# BLOCK8.net
KiCad netlist of a schematic drawn in Altium Designer
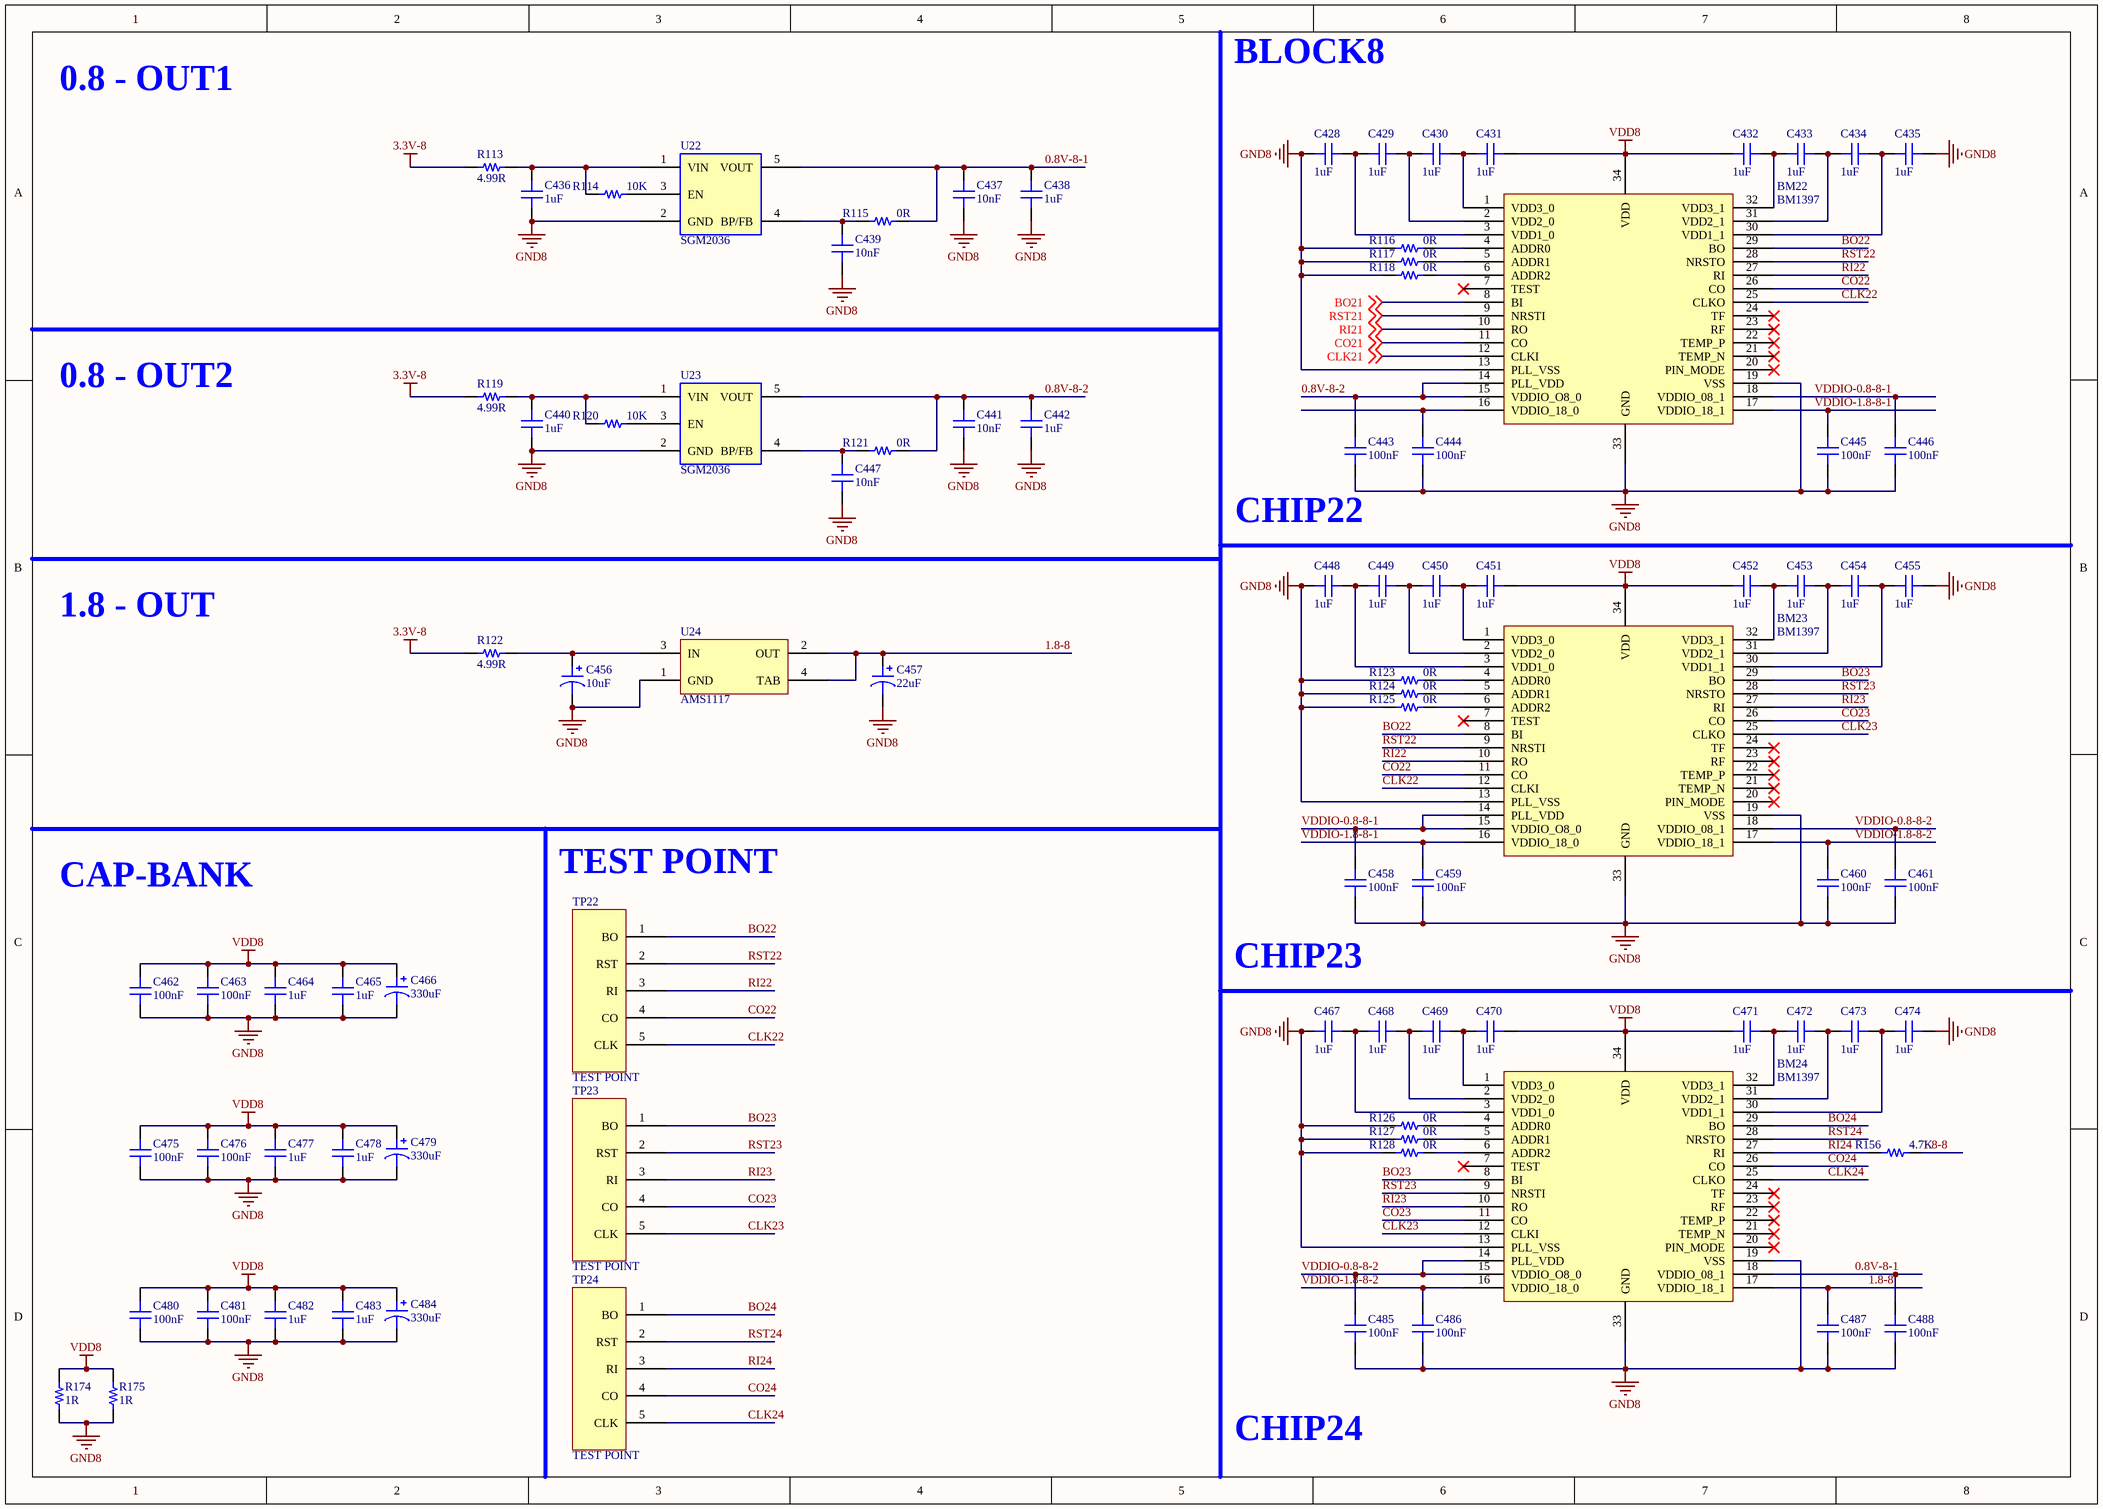
[diagram p0: BLOCK8.SchDoc]

(export (version "E")
  (design (tool "Eeschema 10.0.6"))
  (components
    (comp (ref "BM22") (value "BM1397") (footprint "BM1387") (libsource (lib "Miner_8TH") (part "BM1397_1")))
    (comp (ref "BM23") (value "BM1397") (footprint "BM1387") (libsource (lib "Miner_8TH") (part "BM1397_1")))
    (comp (ref "BM24") (value "BM1397") (footprint "BM1387") (libsource (lib "Miner_8TH") (part "BM1397_1")))
    (comp (ref "C428") (value "1uF") (footprint "CAP-SMD-0603") (libsource (lib "Miner_8TH") (part "CAP")))
    (comp (ref "C429") (value "1uF") (footprint "CAP-SMD-0603") (libsource (lib "Miner_8TH") (part "CAP")))
    (comp (ref "C430") (value "1uF") (footprint "CAP-SMD-0603") (libsource (lib "Miner_8TH") (part "CAP")))
    (comp (ref "C431") (value "1uF") (footprint "CAP-SMD-0603") (libsource (lib "Miner_8TH") (part "CAP")))
    (comp (ref "C432") (value "1uF") (footprint "CAP-SMD-0603") (libsource (lib "Miner_8TH") (part "CAP")))
    (comp (ref "C433") (value "1uF") (footprint "CAP-SMD-0603") (libsource (lib "Miner_8TH") (part "CAP")))
    (comp (ref "C434") (value "1uF") (footprint "CAP-SMD-0603") (libsource (lib "Miner_8TH") (part "CAP")))
    (comp (ref "C435") (value "1uF") (footprint "CAP-SMD-0603") (libsource (lib "Miner_8TH") (part "CAP")))
    (comp (ref "C436") (value "1uF") (footprint "CAP_SMD_0805") (libsource (lib "Miner_8TH") (part "CAP")))
    (comp (ref "C437") (value "10nF") (footprint "CAP_SMD_0805") (libsource (lib "Miner_8TH") (part "CAP")))
    (comp (ref "C438") (value "1uF") (footprint "CAP_SMD_0805") (libsource (lib "Miner_8TH") (part "CAP")))
    (comp (ref "C439") (value "10nF") (footprint "CAP_SMD_0805") (libsource (lib "Miner_8TH") (part "CAP")))
    (comp (ref "C440") (value "1uF") (footprint "CAP_SMD_0805") (libsource (lib "Miner_8TH") (part "CAP")))
    (comp (ref "C441") (value "10nF") (footprint "CAP_SMD_0805") (libsource (lib "Miner_8TH") (part "CAP")))
    (comp (ref "C442") (value "1uF") (footprint "CAP_SMD_0805") (libsource (lib "Miner_8TH") (part "CAP")))
    (comp (ref "C443") (value "100nF") (footprint "CAP_SMD_0805") (libsource (lib "Miner_8TH") (part "CAP")))
    (comp (ref "C444") (value "100nF") (footprint "CAP_SMD_0805") (libsource (lib "Miner_8TH") (part "CAP")))
    (comp (ref "C445") (value "100nF") (footprint "CAP_SMD_0805") (libsource (lib "Miner_8TH") (part "CAP")))
    (comp (ref "C446") (value "100nF") (footprint "CAP_SMD_0805") (libsource (lib "Miner_8TH") (part "CAP")))
    (comp (ref "C447") (value "10nF") (footprint "CAP_SMD_0805") (libsource (lib "Miner_8TH") (part "CAP")))
    (comp (ref "C448") (value "1uF") (footprint "CAP-SMD-0603") (libsource (lib "Miner_8TH") (part "CAP")))
    (comp (ref "C449") (value "1uF") (footprint "CAP-SMD-0603") (libsource (lib "Miner_8TH") (part "CAP")))
    (comp (ref "C450") (value "1uF") (footprint "CAP-SMD-0603") (libsource (lib "Miner_8TH") (part "CAP")))
    (comp (ref "C451") (value "1uF") (footprint "CAP-SMD-0603") (libsource (lib "Miner_8TH") (part "CAP")))
    (comp (ref "C452") (value "1uF") (footprint "CAP-SMD-0603") (libsource (lib "Miner_8TH") (part "CAP")))
    (comp (ref "C453") (value "1uF") (footprint "CAP-SMD-0603") (libsource (lib "Miner_8TH") (part "CAP")))
    (comp (ref "C454") (value "1uF") (footprint "CAP-SMD-0603") (libsource (lib "Miner_8TH") (part "CAP")))
    (comp (ref "C455") (value "1uF") (footprint "CAP-SMD-0603") (libsource (lib "Miner_8TH") (part "CAP")))
    (comp (ref "C456")
      (value "10uF")
      (footprint "CAP-TAN-CASE-A")
      (libsource (lib "Miner_8TH") (part "POLARIZED CAP"))
    )
    (comp (ref "C457")
      (value "22uF")
      (footprint "CAP-TAN-CASE-A")
      (libsource (lib "Miner_8TH") (part "POLARIZED CAP"))
    )
    (comp (ref "C458") (value "100nF") (footprint "CAP_SMD_0805") (libsource (lib "Miner_8TH") (part "CAP")))
    (comp (ref "C459") (value "100nF") (footprint "CAP_SMD_0805") (libsource (lib "Miner_8TH") (part "CAP")))
    (comp (ref "C460") (value "100nF") (footprint "CAP_SMD_0805") (libsource (lib "Miner_8TH") (part "CAP")))
    (comp (ref "C461") (value "100nF") (footprint "CAP_SMD_0805") (libsource (lib "Miner_8TH") (part "CAP")))
    (comp (ref "C462") (value "100nF") (footprint "CAP_SMD_0805") (libsource (lib "Miner_8TH") (part "CAP")))
    (comp (ref "C463") (value "100nF") (footprint "CAP_SMD_0805") (libsource (lib "Miner_8TH") (part "CAP")))
    (comp (ref "C464") (value "1uF") (footprint "CAP_SMD_0805") (libsource (lib "Miner_8TH") (part "CAP")))
    (comp (ref "C465") (value "1uF") (footprint "CAP_SMD_0805") (libsource (lib "Miner_8TH") (part "CAP")))
    (comp (ref "C466")
      (value "330uF")
      (footprint "CAP-TAN-CASE-E")
      (libsource (lib "Miner_8TH") (part "POLARIZED CAP"))
    )
    (comp (ref "C467") (value "1uF") (footprint "CAP-SMD-0603") (libsource (lib "Miner_8TH") (part "CAP")))
    (comp (ref "C468") (value "1uF") (footprint "CAP-SMD-0603") (libsource (lib "Miner_8TH") (part "CAP")))
    (comp (ref "C469") (value "1uF") (footprint "CAP-SMD-0603") (libsource (lib "Miner_8TH") (part "CAP")))
    (comp (ref "C470") (value "1uF") (footprint "CAP-SMD-0603") (libsource (lib "Miner_8TH") (part "CAP")))
    (comp (ref "C471") (value "1uF") (footprint "CAP-SMD-0603") (libsource (lib "Miner_8TH") (part "CAP")))
    (comp (ref "C472") (value "1uF") (footprint "CAP-SMD-0603") (libsource (lib "Miner_8TH") (part "CAP")))
    (comp (ref "C473") (value "1uF") (footprint "CAP-SMD-0603") (libsource (lib "Miner_8TH") (part "CAP")))
    (comp (ref "C474") (value "1uF") (footprint "CAP-SMD-0603") (libsource (lib "Miner_8TH") (part "CAP")))
    (comp (ref "C475") (value "100nF") (footprint "CAP_SMD_0805") (libsource (lib "Miner_8TH") (part "CAP")))
    (comp (ref "C476") (value "100nF") (footprint "CAP_SMD_0805") (libsource (lib "Miner_8TH") (part "CAP")))
    (comp (ref "C477") (value "1uF") (footprint "CAP_SMD_0805") (libsource (lib "Miner_8TH") (part "CAP")))
    (comp (ref "C478") (value "1uF") (footprint "CAP_SMD_0805") (libsource (lib "Miner_8TH") (part "CAP")))
    (comp (ref "C479")
      (value "330uF")
      (footprint "CAP-TAN-CASE-E")
      (libsource (lib "Miner_8TH") (part "POLARIZED CAP"))
    )
    (comp (ref "C480") (value "100nF") (footprint "CAP_SMD_0805") (libsource (lib "Miner_8TH") (part "CAP")))
    (comp (ref "C481") (value "100nF") (footprint "CAP_SMD_0805") (libsource (lib "Miner_8TH") (part "CAP")))
    (comp (ref "C482") (value "1uF") (footprint "CAP_SMD_0805") (libsource (lib "Miner_8TH") (part "CAP")))
    (comp (ref "C483") (value "1uF") (footprint "CAP_SMD_0805") (libsource (lib "Miner_8TH") (part "CAP")))
    (comp (ref "C484")
      (value "330uF")
      (footprint "CAP-TAN-CASE-E")
      (libsource (lib "Miner_8TH") (part "POLARIZED CAP"))
    )
    (comp (ref "C485") (value "100nF") (footprint "CAP_SMD_0805") (libsource (lib "Miner_8TH") (part "CAP")))
    (comp (ref "C486") (value "100nF") (footprint "CAP_SMD_0805") (libsource (lib "Miner_8TH") (part "CAP")))
    (comp (ref "C487") (value "100nF") (footprint "CAP_SMD_0805") (libsource (lib "Miner_8TH") (part "CAP")))
    (comp (ref "C488") (value "100nF") (footprint "CAP_SMD_0805") (libsource (lib "Miner_8TH") (part "CAP")))
    (comp (ref "R113") (value "4.99R") (footprint "RES-SMD-1206") (libsource (lib "Miner_8TH") (part "RES")))
    (comp (ref "R114") (value "10K") (footprint "RES-SMD-0402") (libsource (lib "Miner_8TH") (part "RES")))
    (comp (ref "R115") (value "0R") (footprint "RES-SMD-0402") (libsource (lib "Miner_8TH") (part "RES")))
    (comp (ref "R116") (value "0R") (footprint "RES-SMD-0402") (libsource (lib "Miner_8TH") (part "RES")))
    (comp (ref "R117") (value "0R") (footprint "RES-SMD-0402") (libsource (lib "Miner_8TH") (part "RES")))
    (comp (ref "R118") (value "0R") (footprint "RES-SMD-0402") (libsource (lib "Miner_8TH") (part "RES")))
    (comp (ref "R119") (value "4.99R") (footprint "RES-SMD-1206") (libsource (lib "Miner_8TH") (part "RES")))
    (comp (ref "R120") (value "10K") (footprint "RES-SMD-0402") (libsource (lib "Miner_8TH") (part "RES")))
    (comp (ref "R121") (value "0R") (footprint "RES-SMD-0402") (libsource (lib "Miner_8TH") (part "RES")))
    (comp (ref "R122") (value "4.99R") (footprint "RES-SMD-1206") (libsource (lib "Miner_8TH") (part "RES")))
    (comp (ref "R123") (value "0R") (footprint "RES-SMD-0402") (libsource (lib "Miner_8TH") (part "RES")))
    (comp (ref "R124") (value "0R") (footprint "RES-SMD-0402") (libsource (lib "Miner_8TH") (part "RES")))
    (comp (ref "R125") (value "0R") (footprint "RES-SMD-0402") (libsource (lib "Miner_8TH") (part "RES")))
    (comp (ref "R126") (value "0R") (footprint "RES-SMD-0402") (libsource (lib "Miner_8TH") (part "RES")))
    (comp (ref "R127") (value "0R") (footprint "RES-SMD-0402") (libsource (lib "Miner_8TH") (part "RES")))
    (comp (ref "R128") (value "0R") (footprint "RES-SMD-0402") (libsource (lib "Miner_8TH") (part "RES")))
    (comp (ref "R156") (value "4.7K") (footprint "RES-SMD-0402") (libsource (lib "Miner_8TH") (part "RES")))
    (comp (ref "R174") (value "1R") (footprint "RES-SMD-1210") (libsource (lib "Miner_8TH") (part "RES")))
    (comp (ref "R175") (value "1R") (footprint "RES-SMD-1210") (libsource (lib "Miner_8TH") (part "RES")))
    (comp (ref "TP22")
      (value "TEST POINT")
      (footprint "TEST_POINT")
      (libsource (lib "Miner_8TH") (part "TEST POINT"))
    )
    (comp (ref "TP23")
      (value "TEST POINT")
      (footprint "TEST_POINT")
      (libsource (lib "Miner_8TH") (part "TEST POINT"))
    )
    (comp (ref "TP24")
      (value "TEST POINT")
      (footprint "TEST_POINT")
      (libsource (lib "Miner_8TH") (part "TEST POINT"))
    )
    (comp (ref "U22")
      (value "SGM2036")
      (footprint "SOT23-5PIN")
      (libsource (lib "Miner_8TH") (part "SGM2036"))
    )
    (comp (ref "U23")
      (value "SGM2036")
      (footprint "SOT23-5PIN")
      (libsource (lib "Miner_8TH") (part "SGM2036"))
    )
    (comp (ref "U24") (value "AMS1117") (footprint "AMS1117") (libsource (lib "Miner_8TH") (part "AMS1117")))
  )
  (nets
    (net (code "1") (name "/0.8V-8-1") (class "Default")
      (node (ref "BM24") (pin "18") (pinfunction "VDDIO_08_1_18") (pintype "passive"))
      (node (ref "C437") (pin "2") (pinfunction "2_2") (pintype "passive"))
      (node (ref "C438") (pin "2") (pinfunction "2_2") (pintype "passive"))
      (node (ref "C488") (pin "2") (pinfunction "2_2") (pintype "passive"))
      (node (ref "R115") (pin "2") (pinfunction "2_2") (pintype "passive"))
      (node (ref "U22") (pin "5") (pinfunction "VOUT_5") (pintype "passive"))
    )
    (net (code "2") (name "/0.8V-8-2") (class "Default")
      (node (ref "BM22") (pin "14") (pinfunction "PLL_VDD_14") (pintype "passive"))
      (node (ref "BM22") (pin "15") (pinfunction "VDDIO_O8_0_15") (pintype "passive"))
      (node (ref "C441") (pin "2") (pinfunction "2_2") (pintype "passive"))
      (node (ref "C442") (pin "2") (pinfunction "2_2") (pintype "passive"))
      (node (ref "C443") (pin "2") (pinfunction "2_2") (pintype "passive"))
      (node (ref "R121") (pin "2") (pinfunction "2_2") (pintype "passive"))
      (node (ref "U23") (pin "5") (pinfunction "VOUT_5") (pintype "passive"))
    )
    (net (code "3") (name "/1.8-8") (class "Default")
      (node (ref "BM24") (pin "17") (pinfunction "VDDIO_18_1_17") (pintype "passive"))
      (node (ref "C457") (pin "1") (pinfunction "1_1") (pintype "passive"))
      (node (ref "C487") (pin "2") (pinfunction "2_2") (pintype "passive"))
      (node (ref "R156") (pin "2") (pinfunction "2_2") (pintype "passive"))
      (node (ref "U24") (pin "2") (pinfunction "OUT_2") (pintype "passive"))
      (node (ref "U24") (pin "4") (pinfunction "TAB_4") (pintype "passive"))
    )
    (net (code "4") (name "/BO22") (class "Default")
      (node (ref "BM22") (pin "29") (pinfunction "BO_29") (pintype "passive"))
      (node (ref "BM23") (pin "8") (pinfunction "BI_8") (pintype "passive"))
      (node (ref "TP22") (pin "1") (pinfunction "BO_1") (pintype "passive"))
    )
    (net (code "5") (name "/BO23") (class "Default")
      (node (ref "BM23") (pin "29") (pinfunction "BO_29") (pintype "passive"))
      (node (ref "BM24") (pin "8") (pinfunction "BI_8") (pintype "passive"))
      (node (ref "TP23") (pin "1") (pinfunction "BO_1") (pintype "passive"))
    )
    (net (code "6") (name "/BO24") (class "Default")
      (node (ref "BM24") (pin "29") (pinfunction "BO_29") (pintype "passive"))
      (node (ref "TP24") (pin "1") (pinfunction "BO_1") (pintype "passive"))
    )
    (net (code "7") (name "/CLK22") (class "Default")
      (node (ref "BM22") (pin "25") (pinfunction "CLKO_25") (pintype "passive"))
      (node (ref "BM23") (pin "12") (pinfunction "CLKI_12") (pintype "passive"))
      (node (ref "TP22") (pin "5") (pinfunction "CLK_5") (pintype "passive"))
    )
    (net (code "8") (name "/CLK23") (class "Default")
      (node (ref "BM23") (pin "25") (pinfunction "CLKO_25") (pintype "passive"))
      (node (ref "BM24") (pin "12") (pinfunction "CLKI_12") (pintype "passive"))
      (node (ref "TP23") (pin "5") (pinfunction "CLK_5") (pintype "passive"))
    )
    (net (code "9") (name "/CLK24") (class "Default")
      (node (ref "BM24") (pin "25") (pinfunction "CLKO_25") (pintype "passive"))
      (node (ref "TP24") (pin "5") (pinfunction "CLK_5") (pintype "passive"))
    )
    (net (code "10") (name "/CO22") (class "Default")
      (node (ref "BM22") (pin "26") (pinfunction "CO_26") (pintype "passive"))
      (node (ref "BM23") (pin "11") (pinfunction "CO_11") (pintype "passive"))
      (node (ref "TP22") (pin "4") (pinfunction "CO_4") (pintype "passive"))
    )
    (net (code "11") (name "/CO23") (class "Default")
      (node (ref "BM23") (pin "26") (pinfunction "CO_26") (pintype "passive"))
      (node (ref "BM24") (pin "11") (pinfunction "CO_11") (pintype "passive"))
      (node (ref "TP23") (pin "4") (pinfunction "CO_4") (pintype "passive"))
    )
    (net (code "12") (name "/CO24") (class "Default")
      (node (ref "BM24") (pin "26") (pinfunction "CO_26") (pintype "passive"))
      (node (ref "TP24") (pin "4") (pinfunction "CO_4") (pintype "passive"))
    )
    (net (code "13") (name "/RI22") (class "Default")
      (node (ref "BM22") (pin "27") (pinfunction "RI_27") (pintype "passive"))
      (node (ref "BM23") (pin "10") (pinfunction "RO_10") (pintype "passive"))
      (node (ref "TP22") (pin "3") (pinfunction "RI_3") (pintype "passive"))
    )
    (net (code "14") (name "/RI23") (class "Default")
      (node (ref "BM23") (pin "27") (pinfunction "RI_27") (pintype "passive"))
      (node (ref "BM24") (pin "10") (pinfunction "RO_10") (pintype "passive"))
      (node (ref "TP23") (pin "3") (pinfunction "RI_3") (pintype "passive"))
    )
    (net (code "15") (name "/RI24") (class "Default")
      (node (ref "BM24") (pin "27") (pinfunction "RI_27") (pintype "passive"))
      (node (ref "R156") (pin "1") (pinfunction "1_1") (pintype "passive"))
      (node (ref "TP24") (pin "3") (pinfunction "RI_3") (pintype "passive"))
    )
    (net (code "16") (name "/RST22") (class "Default")
      (node (ref "BM22") (pin "28") (pinfunction "NRSTO_28") (pintype "passive"))
      (node (ref "BM23") (pin "9") (pinfunction "NRSTI_9") (pintype "passive"))
      (node (ref "TP22") (pin "2") (pinfunction "RST_2") (pintype "passive"))
    )
    (net (code "17") (name "/RST23") (class "Default")
      (node (ref "BM23") (pin "28") (pinfunction "NRSTO_28") (pintype "passive"))
      (node (ref "BM24") (pin "9") (pinfunction "NRSTI_9") (pintype "passive"))
      (node (ref "TP23") (pin "2") (pinfunction "RST_2") (pintype "passive"))
    )
    (net (code "18") (name "/RST24") (class "Default")
      (node (ref "BM24") (pin "28") (pinfunction "NRSTO_28") (pintype "passive"))
      (node (ref "TP24") (pin "2") (pinfunction "RST_2") (pintype "passive"))
    )
    (net (code "19") (name "/VDDIO-0.8-8-1") (class "Default")
      (node (ref "BM22") (pin "18") (pinfunction "VDDIO_08_1_18") (pintype "passive"))
      (node (ref "BM23") (pin "14") (pinfunction "PLL_VDD_14") (pintype "passive"))
      (node (ref "BM23") (pin "15") (pinfunction "VDDIO_O8_0_15") (pintype "passive"))
      (node (ref "C446") (pin "2") (pinfunction "2_2") (pintype "passive"))
      (node (ref "C458") (pin "2") (pinfunction "2_2") (pintype "passive"))
    )
    (net (code "20") (name "/VDDIO-0.8-8-2") (class "Default")
      (node (ref "BM23") (pin "18") (pinfunction "VDDIO_08_1_18") (pintype "passive"))
      (node (ref "BM24") (pin "14") (pinfunction "PLL_VDD_14") (pintype "passive"))
      (node (ref "BM24") (pin "15") (pinfunction "VDDIO_O8_0_15") (pintype "passive"))
      (node (ref "C461") (pin "2") (pinfunction "2_2") (pintype "passive"))
      (node (ref "C485") (pin "2") (pinfunction "2_2") (pintype "passive"))
    )
    (net (code "21") (name "/VDDIO-1.8-8-1") (class "Default")
      (node (ref "BM22") (pin "17") (pinfunction "VDDIO_18_1_17") (pintype "passive"))
      (node (ref "BM23") (pin "16") (pinfunction "VDDIO_18_0_16") (pintype "passive"))
      (node (ref "C445") (pin "2") (pinfunction "2_2") (pintype "passive"))
      (node (ref "C459") (pin "2") (pinfunction "2_2") (pintype "passive"))
    )
    (net (code "22") (name "/VDDIO-1.8-8-2") (class "Default")
      (node (ref "BM23") (pin "17") (pinfunction "VDDIO_18_1_17") (pintype "passive"))
      (node (ref "BM24") (pin "16") (pinfunction "VDDIO_18_0_16") (pintype "passive"))
      (node (ref "C460") (pin "2") (pinfunction "2_2") (pintype "passive"))
      (node (ref "C486") (pin "2") (pinfunction "2_2") (pintype "passive"))
    )
    (net (code "23") (name "3.3V-8") (class "Default")
      (node (ref "R113") (pin "1") (pinfunction "1_1") (pintype "passive"))
      (node (ref "R119") (pin "1") (pinfunction "1_1") (pintype "passive"))
      (node (ref "R122") (pin "1") (pinfunction "1_1") (pintype "passive"))
    )
    (net (code "24") (name "BO21") (class "Default")
      (node (ref "BM22") (pin "8") (pinfunction "BI_8") (pintype "passive"))
    )
    (net (code "25") (name "CLK21") (class "Default")
      (node (ref "BM22") (pin "12") (pinfunction "CLKI_12") (pintype "passive"))
    )
    (net (code "26") (name "CO21") (class "Default")
      (node (ref "BM22") (pin "11") (pinfunction "CO_11") (pintype "passive"))
    )
    (net (code "27") (name "GND8") (class "Default")
      (node (ref "BM22") (pin "13") (pinfunction "PLL_VSS_13") (pintype "passive"))
      (node (ref "BM22") (pin "19") (pinfunction "VSS_19") (pintype "passive"))
      (node (ref "BM22") (pin "33") (pinfunction "GND_33") (pintype "passive"))
      (node (ref "BM23") (pin "13") (pinfunction "PLL_VSS_13") (pintype "passive"))
      (node (ref "BM23") (pin "19") (pinfunction "VSS_19") (pintype "passive"))
      (node (ref "BM23") (pin "33") (pinfunction "GND_33") (pintype "passive"))
      (node (ref "BM24") (pin "13") (pinfunction "PLL_VSS_13") (pintype "passive"))
      (node (ref "BM24") (pin "19") (pinfunction "VSS_19") (pintype "passive"))
      (node (ref "BM24") (pin "33") (pinfunction "GND_33") (pintype "passive"))
      (node (ref "C428") (pin "1") (pinfunction "1_1") (pintype "passive"))
      (node (ref "C435") (pin "2") (pinfunction "2_2") (pintype "passive"))
      (node (ref "C436") (pin "1") (pinfunction "1_1") (pintype "passive"))
      (node (ref "C437") (pin "1") (pinfunction "1_1") (pintype "passive"))
      (node (ref "C438") (pin "1") (pinfunction "1_1") (pintype "passive"))
      (node (ref "C439") (pin "1") (pinfunction "1_1") (pintype "passive"))
      (node (ref "C440") (pin "1") (pinfunction "1_1") (pintype "passive"))
      (node (ref "C441") (pin "1") (pinfunction "1_1") (pintype "passive"))
      (node (ref "C442") (pin "1") (pinfunction "1_1") (pintype "passive"))
      (node (ref "C443") (pin "1") (pinfunction "1_1") (pintype "passive"))
      (node (ref "C444") (pin "1") (pinfunction "1_1") (pintype "passive"))
      (node (ref "C445") (pin "1") (pinfunction "1_1") (pintype "passive"))
      (node (ref "C446") (pin "1") (pinfunction "1_1") (pintype "passive"))
      (node (ref "C447") (pin "1") (pinfunction "1_1") (pintype "passive"))
      (node (ref "C448") (pin "1") (pinfunction "1_1") (pintype "passive"))
      (node (ref "C455") (pin "2") (pinfunction "2_2") (pintype "passive"))
      (node (ref "C456") (pin "2") (pinfunction "2_2") (pintype "passive"))
      (node (ref "C457") (pin "2") (pinfunction "2_2") (pintype "passive"))
      (node (ref "C458") (pin "1") (pinfunction "1_1") (pintype "passive"))
      (node (ref "C459") (pin "1") (pinfunction "1_1") (pintype "passive"))
      (node (ref "C460") (pin "1") (pinfunction "1_1") (pintype "passive"))
      (node (ref "C461") (pin "1") (pinfunction "1_1") (pintype "passive"))
      (node (ref "C462") (pin "1") (pinfunction "1_1") (pintype "passive"))
      (node (ref "C463") (pin "1") (pinfunction "1_1") (pintype "passive"))
      (node (ref "C464") (pin "1") (pinfunction "1_1") (pintype "passive"))
      (node (ref "C465") (pin "1") (pinfunction "1_1") (pintype "passive"))
      (node (ref "C466") (pin "2") (pinfunction "2_2") (pintype "passive"))
      (node (ref "C467") (pin "1") (pinfunction "1_1") (pintype "passive"))
      (node (ref "C474") (pin "2") (pinfunction "2_2") (pintype "passive"))
      (node (ref "C475") (pin "1") (pinfunction "1_1") (pintype "passive"))
      (node (ref "C476") (pin "1") (pinfunction "1_1") (pintype "passive"))
      (node (ref "C477") (pin "1") (pinfunction "1_1") (pintype "passive"))
      (node (ref "C478") (pin "1") (pinfunction "1_1") (pintype "passive"))
      (node (ref "C479") (pin "2") (pinfunction "2_2") (pintype "passive"))
      (node (ref "C480") (pin "1") (pinfunction "1_1") (pintype "passive"))
      (node (ref "C481") (pin "1") (pinfunction "1_1") (pintype "passive"))
      (node (ref "C482") (pin "1") (pinfunction "1_1") (pintype "passive"))
      (node (ref "C483") (pin "1") (pinfunction "1_1") (pintype "passive"))
      (node (ref "C484") (pin "2") (pinfunction "2_2") (pintype "passive"))
      (node (ref "C485") (pin "1") (pinfunction "1_1") (pintype "passive"))
      (node (ref "C486") (pin "1") (pinfunction "1_1") (pintype "passive"))
      (node (ref "C487") (pin "1") (pinfunction "1_1") (pintype "passive"))
      (node (ref "C488") (pin "1") (pinfunction "1_1") (pintype "passive"))
      (node (ref "R116") (pin "1") (pinfunction "1_1") (pintype "passive"))
      (node (ref "R117") (pin "1") (pinfunction "1_1") (pintype "passive"))
      (node (ref "R118") (pin "1") (pinfunction "1_1") (pintype "passive"))
      (node (ref "R123") (pin "1") (pinfunction "1_1") (pintype "passive"))
      (node (ref "R124") (pin "1") (pinfunction "1_1") (pintype "passive"))
      (node (ref "R125") (pin "1") (pinfunction "1_1") (pintype "passive"))
      (node (ref "R126") (pin "1") (pinfunction "1_1") (pintype "passive"))
      (node (ref "R127") (pin "1") (pinfunction "1_1") (pintype "passive"))
      (node (ref "R128") (pin "1") (pinfunction "1_1") (pintype "passive"))
      (node (ref "R174") (pin "1") (pinfunction "1_1") (pintype "passive"))
      (node (ref "R175") (pin "1") (pinfunction "1_1") (pintype "passive"))
      (node (ref "U22") (pin "2") (pinfunction "GND_2") (pintype "passive"))
      (node (ref "U23") (pin "2") (pinfunction "GND_2") (pintype "passive"))
      (node (ref "U24") (pin "1") (pinfunction "GND_1") (pintype "passive"))
    )
    (net (code "28") (name "Net-(BM22-ADDR0)") (class "Default")
      (node (ref "BM22") (pin "4") (pinfunction "ADDR0_4") (pintype "passive"))
      (node (ref "R116") (pin "2") (pinfunction "2_2") (pintype "passive"))
    )
    (net (code "29") (name "Net-(BM22-ADDR1)") (class "Default")
      (node (ref "BM22") (pin "5") (pinfunction "ADDR1_5") (pintype "passive"))
      (node (ref "R117") (pin "2") (pinfunction "2_2") (pintype "passive"))
    )
    (net (code "30") (name "Net-(BM22-ADDR2)") (class "Default")
      (node (ref "BM22") (pin "6") (pinfunction "ADDR2_6") (pintype "passive"))
      (node (ref "R118") (pin "2") (pinfunction "2_2") (pintype "passive"))
    )
    (net (code "31") (name "Net-(BM22-VDD1_0)") (class "Default")
      (node (ref "BM22") (pin "3") (pinfunction "VDD1_0_3") (pintype "passive"))
      (node (ref "C428") (pin "2") (pinfunction "2_2") (pintype "passive"))
      (node (ref "C429") (pin "1") (pinfunction "1_1") (pintype "passive"))
    )
    (net (code "32") (name "Net-(BM22-VDD1_1)") (class "Default")
      (node (ref "BM22") (pin "30") (pinfunction "VDD1_1_30") (pintype "passive"))
      (node (ref "C434") (pin "2") (pinfunction "2_2") (pintype "passive"))
      (node (ref "C435") (pin "1") (pinfunction "1_1") (pintype "passive"))
    )
    (net (code "33") (name "Net-(BM22-VDD2_0)") (class "Default")
      (node (ref "BM22") (pin "2") (pinfunction "VDD2_0_2") (pintype "passive"))
      (node (ref "C429") (pin "2") (pinfunction "2_2") (pintype "passive"))
      (node (ref "C430") (pin "1") (pinfunction "1_1") (pintype "passive"))
    )
    (net (code "34") (name "Net-(BM22-VDD2_1)") (class "Default")
      (node (ref "BM22") (pin "31") (pinfunction "VDD2_1_31") (pintype "passive"))
      (node (ref "C433") (pin "2") (pinfunction "2_2") (pintype "passive"))
      (node (ref "C434") (pin "1") (pinfunction "1_1") (pintype "passive"))
    )
    (net (code "35") (name "Net-(BM22-VDD3_0)") (class "Default")
      (node (ref "BM22") (pin "1") (pinfunction "VDD3_0_1") (pintype "passive"))
      (node (ref "C430") (pin "2") (pinfunction "2_2") (pintype "passive"))
      (node (ref "C431") (pin "1") (pinfunction "1_1") (pintype "passive"))
    )
    (net (code "36") (name "Net-(BM22-VDD3_1)") (class "Default")
      (node (ref "BM22") (pin "32") (pinfunction "VDD3_1_32") (pintype "passive"))
      (node (ref "C432") (pin "2") (pinfunction "2_2") (pintype "passive"))
      (node (ref "C433") (pin "1") (pinfunction "1_1") (pintype "passive"))
    )
    (net (code "37") (name "Net-(BM22-VDDIO_18_0)") (class "Default")
      (node (ref "BM22") (pin "16") (pinfunction "VDDIO_18_0_16") (pintype "passive"))
      (node (ref "C444") (pin "2") (pinfunction "2_2") (pintype "passive"))
    )
    (net (code "38") (name "Net-(BM23-ADDR0)") (class "Default")
      (node (ref "BM23") (pin "4") (pinfunction "ADDR0_4") (pintype "passive"))
      (node (ref "R123") (pin "2") (pinfunction "2_2") (pintype "passive"))
    )
    (net (code "39") (name "Net-(BM23-ADDR1)") (class "Default")
      (node (ref "BM23") (pin "5") (pinfunction "ADDR1_5") (pintype "passive"))
      (node (ref "R124") (pin "2") (pinfunction "2_2") (pintype "passive"))
    )
    (net (code "40") (name "Net-(BM23-ADDR2)") (class "Default")
      (node (ref "BM23") (pin "6") (pinfunction "ADDR2_6") (pintype "passive"))
      (node (ref "R125") (pin "2") (pinfunction "2_2") (pintype "passive"))
    )
    (net (code "41") (name "Net-(BM23-VDD1_0)") (class "Default")
      (node (ref "BM23") (pin "3") (pinfunction "VDD1_0_3") (pintype "passive"))
      (node (ref "C448") (pin "2") (pinfunction "2_2") (pintype "passive"))
      (node (ref "C449") (pin "1") (pinfunction "1_1") (pintype "passive"))
    )
    (net (code "42") (name "Net-(BM23-VDD1_1)") (class "Default")
      (node (ref "BM23") (pin "30") (pinfunction "VDD1_1_30") (pintype "passive"))
      (node (ref "C454") (pin "2") (pinfunction "2_2") (pintype "passive"))
      (node (ref "C455") (pin "1") (pinfunction "1_1") (pintype "passive"))
    )
    (net (code "43") (name "Net-(BM23-VDD2_0)") (class "Default")
      (node (ref "BM23") (pin "2") (pinfunction "VDD2_0_2") (pintype "passive"))
      (node (ref "C449") (pin "2") (pinfunction "2_2") (pintype "passive"))
      (node (ref "C450") (pin "1") (pinfunction "1_1") (pintype "passive"))
    )
    (net (code "44") (name "Net-(BM23-VDD2_1)") (class "Default")
      (node (ref "BM23") (pin "31") (pinfunction "VDD2_1_31") (pintype "passive"))
      (node (ref "C453") (pin "2") (pinfunction "2_2") (pintype "passive"))
      (node (ref "C454") (pin "1") (pinfunction "1_1") (pintype "passive"))
    )
    (net (code "45") (name "Net-(BM23-VDD3_0)") (class "Default")
      (node (ref "BM23") (pin "1") (pinfunction "VDD3_0_1") (pintype "passive"))
      (node (ref "C450") (pin "2") (pinfunction "2_2") (pintype "passive"))
      (node (ref "C451") (pin "1") (pinfunction "1_1") (pintype "passive"))
    )
    (net (code "46") (name "Net-(BM23-VDD3_1)") (class "Default")
      (node (ref "BM23") (pin "32") (pinfunction "VDD3_1_32") (pintype "passive"))
      (node (ref "C452") (pin "2") (pinfunction "2_2") (pintype "passive"))
      (node (ref "C453") (pin "1") (pinfunction "1_1") (pintype "passive"))
    )
    (net (code "47") (name "Net-(BM24-ADDR0)") (class "Default")
      (node (ref "BM24") (pin "4") (pinfunction "ADDR0_4") (pintype "passive"))
      (node (ref "R126") (pin "2") (pinfunction "2_2") (pintype "passive"))
    )
    (net (code "48") (name "Net-(BM24-ADDR1)") (class "Default")
      (node (ref "BM24") (pin "5") (pinfunction "ADDR1_5") (pintype "passive"))
      (node (ref "R127") (pin "2") (pinfunction "2_2") (pintype "passive"))
    )
    (net (code "49") (name "Net-(BM24-ADDR2)") (class "Default")
      (node (ref "BM24") (pin "6") (pinfunction "ADDR2_6") (pintype "passive"))
      (node (ref "R128") (pin "2") (pinfunction "2_2") (pintype "passive"))
    )
    (net (code "50") (name "Net-(BM24-VDD1_0)") (class "Default")
      (node (ref "BM24") (pin "3") (pinfunction "VDD1_0_3") (pintype "passive"))
      (node (ref "C467") (pin "2") (pinfunction "2_2") (pintype "passive"))
      (node (ref "C468") (pin "1") (pinfunction "1_1") (pintype "passive"))
    )
    (net (code "51") (name "Net-(BM24-VDD1_1)") (class "Default")
      (node (ref "BM24") (pin "30") (pinfunction "VDD1_1_30") (pintype "passive"))
      (node (ref "C473") (pin "2") (pinfunction "2_2") (pintype "passive"))
      (node (ref "C474") (pin "1") (pinfunction "1_1") (pintype "passive"))
    )
    (net (code "52") (name "Net-(BM24-VDD2_0)") (class "Default")
      (node (ref "BM24") (pin "2") (pinfunction "VDD2_0_2") (pintype "passive"))
      (node (ref "C468") (pin "2") (pinfunction "2_2") (pintype "passive"))
      (node (ref "C469") (pin "1") (pinfunction "1_1") (pintype "passive"))
    )
    (net (code "53") (name "Net-(BM24-VDD2_1)") (class "Default")
      (node (ref "BM24") (pin "31") (pinfunction "VDD2_1_31") (pintype "passive"))
      (node (ref "C472") (pin "2") (pinfunction "2_2") (pintype "passive"))
      (node (ref "C473") (pin "1") (pinfunction "1_1") (pintype "passive"))
    )
    (net (code "54") (name "Net-(BM24-VDD3_0)") (class "Default")
      (node (ref "BM24") (pin "1") (pinfunction "VDD3_0_1") (pintype "passive"))
      (node (ref "C469") (pin "2") (pinfunction "2_2") (pintype "passive"))
      (node (ref "C470") (pin "1") (pinfunction "1_1") (pintype "passive"))
    )
    (net (code "55") (name "Net-(BM24-VDD3_1)") (class "Default")
      (node (ref "BM24") (pin "32") (pinfunction "VDD3_1_32") (pintype "passive"))
      (node (ref "C471") (pin "2") (pinfunction "2_2") (pintype "passive"))
      (node (ref "C472") (pin "1") (pinfunction "1_1") (pintype "passive"))
    )
    (net (code "56") (name "Net-(U22-BP{slash}FB)") (class "Default")
      (node (ref "C439") (pin "2") (pinfunction "2_2") (pintype "passive"))
      (node (ref "R115") (pin "1") (pinfunction "1_1") (pintype "passive"))
      (node (ref "U22") (pin "4") (pinfunction "BP/FB_4") (pintype "passive"))
    )
    (net (code "57") (name "Net-(U22-EN)") (class "Default")
      (node (ref "R114") (pin "2") (pinfunction "2_2") (pintype "passive"))
      (node (ref "U22") (pin "3") (pinfunction "EN_3") (pintype "passive"))
    )
    (net (code "58") (name "Net-(U22-VIN)") (class "Default")
      (node (ref "C436") (pin "2") (pinfunction "2_2") (pintype "passive"))
      (node (ref "R113") (pin "2") (pinfunction "2_2") (pintype "passive"))
      (node (ref "R114") (pin "1") (pinfunction "1_1") (pintype "passive"))
      (node (ref "U22") (pin "1") (pinfunction "VIN_1") (pintype "passive"))
    )
    (net (code "59") (name "Net-(U23-BP{slash}FB)") (class "Default")
      (node (ref "C447") (pin "2") (pinfunction "2_2") (pintype "passive"))
      (node (ref "R121") (pin "1") (pinfunction "1_1") (pintype "passive"))
      (node (ref "U23") (pin "4") (pinfunction "BP/FB_4") (pintype "passive"))
    )
    (net (code "60") (name "Net-(U23-EN)") (class "Default")
      (node (ref "R120") (pin "2") (pinfunction "2_2") (pintype "passive"))
      (node (ref "U23") (pin "3") (pinfunction "EN_3") (pintype "passive"))
    )
    (net (code "61") (name "Net-(U23-VIN)") (class "Default")
      (node (ref "C440") (pin "2") (pinfunction "2_2") (pintype "passive"))
      (node (ref "R119") (pin "2") (pinfunction "2_2") (pintype "passive"))
      (node (ref "R120") (pin "1") (pinfunction "1_1") (pintype "passive"))
      (node (ref "U23") (pin "1") (pinfunction "VIN_1") (pintype "passive"))
    )
    (net (code "62") (name "Net-(U24-IN)") (class "Default")
      (node (ref "C456") (pin "1") (pinfunction "1_1") (pintype "passive"))
      (node (ref "R122") (pin "2") (pinfunction "2_2") (pintype "passive"))
      (node (ref "U24") (pin "3") (pinfunction "IN_3") (pintype "passive"))
    )
    (net (code "63") (name "RI21") (class "Default")
      (node (ref "BM22") (pin "10") (pinfunction "RO_10") (pintype "passive"))
    )
    (net (code "64") (name "RST21") (class "Default")
      (node (ref "BM22") (pin "9") (pinfunction "NRSTI_9") (pintype "passive"))
    )
    (net (code "65") (name "VDD8") (class "Default")
      (node (ref "BM22") (pin "34") (pinfunction "VDD_34") (pintype "passive"))
      (node (ref "BM23") (pin "34") (pinfunction "VDD_34") (pintype "passive"))
      (node (ref "BM24") (pin "34") (pinfunction "VDD_34") (pintype "passive"))
      (node (ref "C431") (pin "2") (pinfunction "2_2") (pintype "passive"))
      (node (ref "C432") (pin "1") (pinfunction "1_1") (pintype "passive"))
      (node (ref "C451") (pin "2") (pinfunction "2_2") (pintype "passive"))
      (node (ref "C452") (pin "1") (pinfunction "1_1") (pintype "passive"))
      (node (ref "C462") (pin "2") (pinfunction "2_2") (pintype "passive"))
      (node (ref "C463") (pin "2") (pinfunction "2_2") (pintype "passive"))
      (node (ref "C464") (pin "2") (pinfunction "2_2") (pintype "passive"))
      (node (ref "C465") (pin "2") (pinfunction "2_2") (pintype "passive"))
      (node (ref "C466") (pin "1") (pinfunction "1_1") (pintype "passive"))
      (node (ref "C470") (pin "2") (pinfunction "2_2") (pintype "passive"))
      (node (ref "C471") (pin "1") (pinfunction "1_1") (pintype "passive"))
      (node (ref "C475") (pin "2") (pinfunction "2_2") (pintype "passive"))
      (node (ref "C476") (pin "2") (pinfunction "2_2") (pintype "passive"))
      (node (ref "C477") (pin "2") (pinfunction "2_2") (pintype "passive"))
      (node (ref "C478") (pin "2") (pinfunction "2_2") (pintype "passive"))
      (node (ref "C479") (pin "1") (pinfunction "1_1") (pintype "passive"))
      (node (ref "C480") (pin "2") (pinfunction "2_2") (pintype "passive"))
      (node (ref "C481") (pin "2") (pinfunction "2_2") (pintype "passive"))
      (node (ref "C482") (pin "2") (pinfunction "2_2") (pintype "passive"))
      (node (ref "C483") (pin "2") (pinfunction "2_2") (pintype "passive"))
      (node (ref "C484") (pin "1") (pinfunction "1_1") (pintype "passive"))
      (node (ref "R174") (pin "2") (pinfunction "2_2") (pintype "passive"))
      (node (ref "R175") (pin "2") (pinfunction "2_2") (pintype "passive"))
    )
    (net (code "66") (name "unconnected-(BM22-PIN_MODE-Pad20)") (class "Default")
      (node (ref "BM22") (pin "20") (pinfunction "PIN_MODE_20") (pintype "passive+no_connect"))
    )
    (net (code "67") (name "unconnected-(BM22-RF-Pad23)") (class "Default")
      (node (ref "BM22") (pin "23") (pinfunction "RF_23") (pintype "passive+no_connect"))
    )
    (net (code "68") (name "unconnected-(BM22-TEMP_N-Pad21)") (class "Default")
      (node (ref "BM22") (pin "21") (pinfunction "TEMP_N_21") (pintype "passive+no_connect"))
    )
    (net (code "69") (name "unconnected-(BM22-TEMP_P-Pad22)") (class "Default")
      (node (ref "BM22") (pin "22") (pinfunction "TEMP_P_22") (pintype "passive+no_connect"))
    )
    (net (code "70") (name "unconnected-(BM22-TEST-Pad7)") (class "Default")
      (node (ref "BM22") (pin "7") (pinfunction "TEST_7") (pintype "passive+no_connect"))
    )
    (net (code "71") (name "unconnected-(BM22-TF-Pad24)") (class "Default")
      (node (ref "BM22") (pin "24") (pinfunction "TF_24") (pintype "passive+no_connect"))
    )
    (net (code "72") (name "unconnected-(BM23-PIN_MODE-Pad20)") (class "Default")
      (node (ref "BM23") (pin "20") (pinfunction "PIN_MODE_20") (pintype "passive+no_connect"))
    )
    (net (code "73") (name "unconnected-(BM23-RF-Pad23)") (class "Default")
      (node (ref "BM23") (pin "23") (pinfunction "RF_23") (pintype "passive+no_connect"))
    )
    (net (code "74") (name "unconnected-(BM23-TEMP_N-Pad21)") (class "Default")
      (node (ref "BM23") (pin "21") (pinfunction "TEMP_N_21") (pintype "passive+no_connect"))
    )
    (net (code "75") (name "unconnected-(BM23-TEMP_P-Pad22)") (class "Default")
      (node (ref "BM23") (pin "22") (pinfunction "TEMP_P_22") (pintype "passive+no_connect"))
    )
    (net (code "76") (name "unconnected-(BM23-TEST-Pad7)") (class "Default")
      (node (ref "BM23") (pin "7") (pinfunction "TEST_7") (pintype "passive+no_connect"))
    )
    (net (code "77") (name "unconnected-(BM23-TF-Pad24)") (class "Default")
      (node (ref "BM23") (pin "24") (pinfunction "TF_24") (pintype "passive+no_connect"))
    )
    (net (code "78") (name "unconnected-(BM24-PIN_MODE-Pad20)") (class "Default")
      (node (ref "BM24") (pin "20") (pinfunction "PIN_MODE_20") (pintype "passive+no_connect"))
    )
    (net (code "79") (name "unconnected-(BM24-RF-Pad23)") (class "Default")
      (node (ref "BM24") (pin "23") (pinfunction "RF_23") (pintype "passive+no_connect"))
    )
    (net (code "80") (name "unconnected-(BM24-TEMP_N-Pad21)") (class "Default")
      (node (ref "BM24") (pin "21") (pinfunction "TEMP_N_21") (pintype "passive+no_connect"))
    )
    (net (code "81") (name "unconnected-(BM24-TEMP_P-Pad22)") (class "Default")
      (node (ref "BM24") (pin "22") (pinfunction "TEMP_P_22") (pintype "passive+no_connect"))
    )
    (net (code "82") (name "unconnected-(BM24-TEST-Pad7)") (class "Default")
      (node (ref "BM24") (pin "7") (pinfunction "TEST_7") (pintype "passive+no_connect"))
    )
    (net (code "83") (name "unconnected-(BM24-TF-Pad24)") (class "Default")
      (node (ref "BM24") (pin "24") (pinfunction "TF_24") (pintype "passive+no_connect"))
    )
  )
)
